# Sheet1.net
KiCad netlist of a schematic drawn in Altium Designer
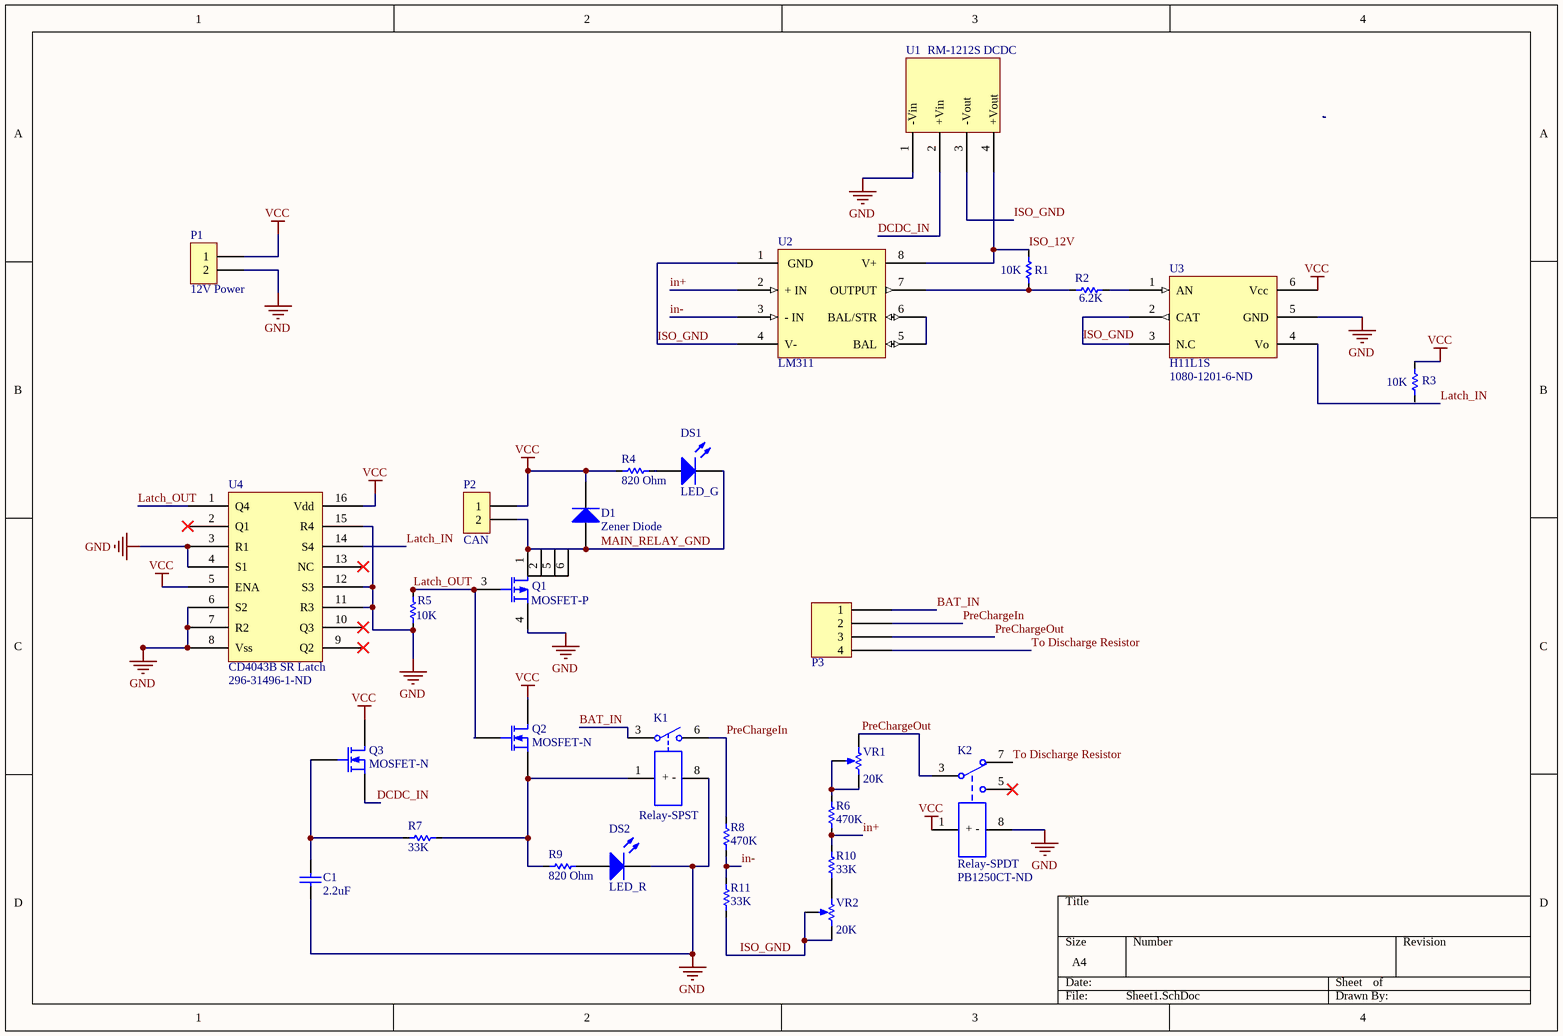
[diagram p0: Sheet1.SchDoc]

(export (version "E")
  (design (tool "Eeschema 10.0.6"))
  (components
    (comp (ref "C1")
      (value "2.2uF")
      (footprint "0603")
      (description "2.2µF ±10% 25V Ceramic Capacitor X5R 0603 (1608 Metric)")
      (fields
        (field (name "MANUFACTURERPARTNUMBER") "GRM188R61E225KA12D")
        (field (name "MANUFACTURER") "Murata Electronics North America")
      )
      (libsource (lib "Schematic Diagrams") (part "CAP CER 2.2UF 25V 10% 0603"))
    )
    (comp (ref "D1")
      (value "Zener Diode")
      (footprint "DO-214AA Diode")
      (description "Zener Diode 16V 5W ±5% Surface Mount DO-214AA (SMB)")
      (fields (field (name "MANUFACTURE PART NUMBER") "SMBJ5353B-TP"))
      (libsource (lib "Schematic Diagrams") (part "Zener Diode"))
    )
    (comp (ref "DS1")
      (value "LED_G")
      (footprint "LED_0603")
      (description "Green LED 0603")
      (fields (field (name "MANUFACTURE PART NUMBER") "LTST-C191KGKT"))
      (libsource (lib "Schematic Diagrams") (part "LED_G"))
    )
    (comp (ref "DS2")
      (value "LED_R")
      (footprint "LED_0603")
      (description "Red LED 0603")
      (fields (field (name "MANUFACTURE PART NUMBER") "LTST-C191KRKT"))
      (libsource (lib "Schematic Diagrams") (part "LED_R"))
    )
    (comp (ref "K1")
      (value "Relay-SPST")
      (footprint "MODULE4")
      (description "Telecom Relay SPST-NO (1 Form A) Surface Mount")
      (fields (field (name "MANUFACTURE PART NUMBER") "1462041-3"))
      (libsource (lib "Schematic Diagrams") (part "Relay-SPST"))
    )
    (comp (ref "K2")
      (value "Relay-SPDT")
      (footprint "RELAY_SPDT")
      (description "Telecom Relay SPDT (1 Form C) Surface Mount")
      (fields
        (field (name "SUPPLIER PART NUMBER 1") "PB1250CT-ND")
        (field (name "MANUFACTURER PART NUMBER") "1462042-9")
      )
      (libsource (lib "Schematic Diagrams") (part "Relay-SPDT"))
    )
    (comp (ref "P1")
      (value "12V Power")
      (footprint "WM9811CT-ND")
      (description "2 Position Receptacle Connector 0.059\" (1.50mm) Surface Mount Tin")
      (fields
        (field (name "DIGIKEY PART NUMBER") "WM9811CT-ND")
        (field (name "MANUFACTURER PART NUMBER") "5025840270")
      )
      (libsource (lib "Schematic Diagrams") (part "2 Position Clik-Mate 12V Connector"))
    )
    (comp (ref "P2")
      (value "CAN")
      (footprint "WM4780CT-ND")
      (description "2 Position Receptacle Connector 0.049\" (1.25mm) Surface Mount Tin")
      (fields
        (field (name "DIGIKEY PART NUMBER") "WM4780CT-ND")
        (field (name "MANUFACTURER PART NUMBER") "5023820270")
      )
      (libsource (lib "Schematic Diagrams") (part "2 Position Clik-Mate CAN Connector"))
    )
    (comp (ref "P3")
      (value "4 Position Clik-Mate HV Surface Mount")
      (footprint "WM2282CT-ND")
      (description "4 Position Receptacle Connector 0.079\" (2.00mm) Surface Mount, Right Angle Tin")
      (libsource (lib "Schematic Diagrams") (part "4 Position Clik-Mate HV Surface Mount"))
    )
    (comp (ref "Q1")
      (value "MOSFET-P")
      (footprint "P-MOSFET")
      (description "MOSFET P-CH 30V 4A SOT23-6")
      (fields
        (field (name "VENDOR PART NUMBER") "497-15521-1-ND")
        (field (name "MANUFACTURE PART NUMBER") "STT4P3LLH6")
      )
      (libsource (lib "Schematic Diagrams") (part "MOSFET-P"))
    )
    (comp (ref "Q2")
      (value "MOSFET-N")
      (footprint "N-CH MOSFET SOT-23")
      (description "MOSFET N-CH 50V 200MA SOT23-3")
      (fields
        (field (name "MANUFACTURE PART NUMBER") "BSS138-7-F")
        (field (name "VENDOR PART NUMBER") "497-3177-1-ND")
      )
      (libsource (lib "Schematic Diagrams") (part "MOSFET-N"))
    )
    (comp (ref "Q3")
      (value "MOSFET-N")
      (footprint "N-CH MOSFET SOT-23")
      (description "MOSFET N-CH 50V 200MA SOT23-3")
      (fields
        (field (name "MANUFACTURE PART NUMBER") "BSS138-7-F")
        (field (name "VENDOR PART NUMBER") "497-3177-1-ND")
      )
      (libsource (lib "Schematic Diagrams") (part "MOSFET-N"))
    )
    (comp (ref "R1")
      (value "10K")
      (footprint "RES_0603")
      (description "RES SMD 10K OHM 1% 1/10W 0603")
      (fields
        (field (name "MANUFACTURE PART NUMBER") "RC0603FR-0710KL")
        (field (name "VENDOR PART NUMBER") "311-10.0KHRCT-ND")
      )
      (libsource (lib "Schematic Diagrams") (part "RES SMD 10K OHM 1% 1/10W 0603"))
    )
    (comp (ref "R2")
      (value "6.2K")
      (footprint "RES_0603")
      (description "RES SMD 6.2K OHM 5% 1/10W 0603")
      (fields
        (field (name "MANUFACTURE PART NUMBER") "RC0603JR-076K2L")
        (field (name "VENDOR PART NUMBER") "311-6.2KGRCT-ND")
      )
      (libsource (lib "Schematic Diagrams") (part "RES SMD 6.2K OHM 5% 1/10W 0603"))
    )
    (comp (ref "R3")
      (value "10K")
      (footprint "RES_0603")
      (description "RES SMD 10K OHM 1% 1/10W 0603")
      (fields
        (field (name "MANUFACTURE PART NUMBER") "RC0603FR-0710KL")
        (field (name "VENDOR PART NUMBER") "311-10.0KHRCT-ND")
      )
      (libsource (lib "Schematic Diagrams") (part "RES SMD 10K OHM 1% 1/10W 0603"))
    )
    (comp (ref "R4")
      (value "820 Ohm")
      (footprint "RES_0603")
      (description "RES SMD 820 OHM 5% 1/4W 0603")
      (fields (field (name "MANUFACTURE PART NUMBER") "ESR03EZPJ821") (field (name "POWER") "1/10W"))
      (libsource (lib "Schematic Diagrams") (part "RES SMD 820 OHM 5% 1/4W 0603"))
    )
    (comp (ref "R5")
      (value "10K")
      (footprint "RES_0603")
      (description "RES SMD 10K OHM 1% 1/10W 0603")
      (fields
        (field (name "MANUFACTURE PART NUMBER") "RC0603FR-0710KL")
        (field (name "VENDOR PART NUMBER") "311-10.0KHRCT-ND")
      )
      (libsource (lib "Schematic Diagrams") (part "RES SMD 10K OHM 1% 1/10W 0603"))
    )
    (comp (ref "R6")
      (value "470K")
      (footprint "RES_0603")
      (description "RES SMD 470K OHM 1% 1/4W 0603")
      (fields (field (name "MANUFACTURE PART NUMBER") "ERJ-PA3F4703V") (field (name "POWER") "0.25W"))
      (libsource (lib "Schematic Diagrams") (part "RES 470K OHM 1% 1/4W 0603"))
    )
    (comp (ref "R7")
      (value "33K")
      (footprint "RES_0603")
      (description "RES 33K OHM 1% 1/4W 0603")
      (fields
        (field (name "MANUFACTURE PART NUMBER") "ERJ-PA3F3302V")
        (field (name "VENDOR PART NUMBER") "P47KBYCT-ND")
      )
      (libsource (lib "Schematic Diagrams") (part "RES 33K OHM 1% 1/4W 0603"))
    )
    (comp (ref "R8")
      (value "470K")
      (footprint "RES_0603")
      (description "RES SMD 470K OHM 1% 1/4W 0603")
      (fields (field (name "MANUFACTURE PART NUMBER") "ERJ-PA3F4703V") (field (name "POWER") "0.25W"))
      (libsource (lib "Schematic Diagrams") (part "RES 470K OHM 1% 1/4W 0603"))
    )
    (comp (ref "R9")
      (value "820 Ohm")
      (footprint "RES_0603")
      (description "RES SMD 820 OHM 5% 1/4W 0603")
      (fields (field (name "MANUFACTURE PART NUMBER") "ESR03EZPJ821") (field (name "POWER") "1/10W"))
      (libsource (lib "Schematic Diagrams") (part "RES SMD 820 OHM 5% 1/4W 0603"))
    )
    (comp (ref "R10")
      (value "33K")
      (footprint "RES_0603")
      (description "RES 33K OHM 1% 1/4W 0603")
      (fields
        (field (name "MANUFACTURE PART NUMBER") "ERJ-PA3F3302V")
        (field (name "VENDOR PART NUMBER") "P47KBYCT-ND")
      )
      (libsource (lib "Schematic Diagrams") (part "RES 33K OHM 1% 1/4W 0603"))
    )
    (comp (ref "R11")
      (value "33K")
      (footprint "RES_0603")
      (description "RES 33K OHM 1% 1/4W 0603")
      (fields
        (field (name "MANUFACTURE PART NUMBER") "ERJ-PA3F3302V")
        (field (name "VENDOR PART NUMBER") "P47KBYCT-ND")
      )
      (libsource (lib "Schematic Diagrams") (part "RES 33K OHM 1% 1/4W 0603"))
    )
    (comp (ref "U1")
      (value "RM-1212S DCDC")
      (footprint "RM-1212S")
      (libsource (lib "Schematic Diagrams") (part "RM-1212S DCDC"))
    )
    (comp (ref "U2") (value "LM311") (footprint "SOIC8") (libsource (lib "Library") (part "LM311")))
    (comp (ref "U3")
      (value "H11L1S")
      (footprint "H11LS")
      (description "OPTOISO 5KV OPEN COLLECTOR 6SMD")
      (fields (field (name "SUPPLIER PART NUMBER 1") "1080-1201-6-ND"))
      (libsource (lib "Schematic Diagrams") (part "H11L1S"))
    )
    (comp (ref "U4")
      (value "CD4043B SR Latch")
      (footprint "CD4043BDR-16SOIC")
      (description "S-R Latch 4 Channel 1:1 IC Tri-State 16-TSSOP")
      (fields (field (name "SUPPLIER PART NUMBER 1") "296-31496-1-ND"))
      (libsource (lib "Schematic Diagrams") (part "CD4043B SR Latch"))
    )
    (comp (ref "VR1")
      (value "20K")
      (footprint "20K POT")
      (description "20k Ohm 0.25W, 1/4W Gull Wing Surface Mount Trimmer Potentiometer")
      (fields (field (name "POWER") "1/4W") (field (name "MANUFACTURE PART NUMBER") "23BR20KLFTR"))
      (libsource (lib "Schematic Diagrams") (part "20k 0.25W Pot"))
    )
    (comp (ref "VR2")
      (value "20K")
      (footprint "20K POT")
      (description "20k Ohm 0.25W, 1/4W Gull Wing Surface Mount Trimmer Potentiometer")
      (fields (field (name "POWER") "1/4W") (field (name "MANUFACTURE PART NUMBER") "23BR20KLFTR"))
      (libsource (lib "Schematic Diagrams") (part "20k 0.25W Pot"))
    )
  )
  (nets
    (net (code "1") (name "/BAT_IN") (class "Default")
      (node (ref "K1") (pin "3") (pinfunction "3_3") (pintype "passive"))
      (node (ref "P3") (pin "1") (pinfunction "1_1") (pintype "passive"))
    )
    (net (code "2") (name "/DCDC_IN") (class "Default")
      (node (ref "Q3") (pin "2") (pinfunction "S_2") (pintype "passive"))
      (node (ref "U1") (pin "2") (pinfunction "+Vin_2") (pintype "passive"))
    )
    (net (code "3") (name "/ISO_12V") (class "Default")
      (node (ref "R1") (pin "2") (pinfunction "2_2") (pintype "passive"))
      (node (ref "U1") (pin "4") (pinfunction "+Vout_4") (pintype "passive"))
      (node (ref "U2") (pin "8") (pinfunction "V+_8") (pintype "power_in"))
    )
    (net (code "4") (name "/ISO_GND") (class "Default")
      (node (ref "R11") (pin "1") (pinfunction "1_1") (pintype "passive"))
      (node (ref "U1") (pin "3") (pinfunction "-Vout_3") (pintype "passive"))
      (node (ref "U2") (pin "1") (pinfunction "GND_1") (pintype "power_in"))
      (node (ref "U2") (pin "4") (pinfunction "V-_4") (pintype "power_in"))
      (node (ref "U3") (pin "2") (pinfunction "CAT_2") (pintype "output"))
      (node (ref "U3") (pin "3") (pinfunction "N.C_3") (pintype "passive"))
      (node (ref "VR2") (pin "2") (pinfunction "TAP_2") (pintype "passive"))
      (node (ref "VR2") (pin "3") (pinfunction "BOT_3") (pintype "passive"))
    )
    (net (code "5") (name "/Latch_IN") (class "Default")
      (node (ref "U3") (pin "4") (pinfunction "Vo_4") (pintype "passive"))
      (node (ref "U4") (pin "14") (pinfunction "S4_14") (pintype "passive"))
    )
    (net (code "6") (name "/Latch_OUT") (class "Default")
      (node (ref "Q1") (pin "3") (pinfunction "G_3") (pintype "passive"))
      (node (ref "Q2") (pin "1") (pinfunction "G_1") (pintype "passive"))
      (node (ref "R5") (pin "2") (pinfunction "2_2") (pintype "passive"))
      (node (ref "U4") (pin "1") (pinfunction "Q4_1") (pintype "passive"))
    )
    (net (code "7") (name "/MAIN_RELAY_GND") (class "Default")
      (node (ref "D1") (pin "1") (pinfunction "A_1") (pintype "passive"))
      (node (ref "DS1") (pin "2") (pinfunction "K_2") (pintype "passive"))
      (node (ref "P2") (pin "2") (pinfunction "2_2") (pintype "passive"))
      (node (ref "Q1") (pin "1") (pinfunction "D_1") (pintype "passive"))
    )
    (net (code "8") (name "/PreChargeIn") (class "Default")
      (node (ref "K1") (pin "6") (pinfunction "6_6") (pintype "passive"))
      (node (ref "P3") (pin "2") (pinfunction "2_2") (pintype "passive"))
      (node (ref "R8") (pin "2") (pinfunction "2_2") (pintype "passive"))
    )
    (net (code "9") (name "/PreChargeOut") (class "Default")
      (node (ref "K2") (pin "3") (pinfunction "3_3") (pintype "passive"))
      (node (ref "P3") (pin "3") (pinfunction "3_3") (pintype "passive"))
      (node (ref "VR1") (pin "1") (pinfunction "TOP_1") (pintype "passive"))
    )
    (net (code "10") (name "/To Discharge Resistor") (class "Default")
      (node (ref "K2") (pin "7") (pinfunction "7_7") (pintype "passive"))
      (node (ref "P3") (pin "4") (pinfunction "4_4") (pintype "passive"))
    )
    (net (code "11") (name "/in+") (class "Default")
      (node (ref "R10") (pin "2") (pinfunction "2_2") (pintype "passive"))
      (node (ref "R6") (pin "1") (pinfunction "1_1") (pintype "passive"))
      (node (ref "U2") (pin "2") (pinfunction "+_IN_2") (pintype "input"))
    )
    (net (code "12") (name "/in-") (class "Default")
      (node (ref "R11") (pin "2") (pinfunction "2_2") (pintype "passive"))
      (node (ref "R8") (pin "1") (pinfunction "1_1") (pintype "passive"))
      (node (ref "U2") (pin "3") (pinfunction "-_IN_3") (pintype "input"))
    )
    (net (code "13") (name "GND") (class "Default")
      (node (ref "C1") (pin "1") (pinfunction "1_1") (pintype "passive"))
      (node (ref "DS2") (pin "2") (pinfunction "K_2") (pintype "passive"))
      (node (ref "K1") (pin "8") (pinfunction "-_8") (pintype "passive"))
      (node (ref "K2") (pin "8") (pinfunction "-_8") (pintype "passive"))
      (node (ref "P1") (pin "2") (pinfunction "2_2") (pintype "passive"))
      (node (ref "Q1") (pin "4") (pinfunction "S_4") (pintype "passive"))
      (node (ref "R5") (pin "1") (pinfunction "1_1") (pintype "passive"))
      (node (ref "U1") (pin "1") (pinfunction "-Vin_1") (pintype "passive"))
      (node (ref "U3") (pin "5") (pinfunction "GND_5") (pintype "passive"))
      (node (ref "U4") (pin "11") (pinfunction "R3_11") (pintype "passive"))
      (node (ref "U4") (pin "12") (pinfunction "S3_12") (pintype "passive"))
      (node (ref "U4") (pin "15") (pinfunction "R4_15") (pintype "passive"))
      (node (ref "U4") (pin "3") (pinfunction "R1_3") (pintype "passive"))
      (node (ref "U4") (pin "4") (pinfunction "S1_4") (pintype "passive"))
      (node (ref "U4") (pin "6") (pinfunction "S2_6") (pintype "passive"))
      (node (ref "U4") (pin "7") (pinfunction "R2_7") (pintype "passive"))
      (node (ref "U4") (pin "8") (pinfunction "Vss_8") (pintype "passive"))
    )
    (net (code "14") (name "Net-(DS1-A)") (class "Default")
      (node (ref "DS1") (pin "1") (pinfunction "A_1") (pintype "passive"))
      (node (ref "R4") (pin "2") (pinfunction "2_2") (pintype "passive"))
    )
    (net (code "15") (name "Net-(DS2-A)") (class "Default")
      (node (ref "DS2") (pin "1") (pinfunction "A_1") (pintype "passive"))
      (node (ref "R9") (pin "2") (pinfunction "2_2") (pintype "passive"))
    )
    (net (code "16") (name "Net-(K1-+)") (class "Default")
      (node (ref "K1") (pin "1") (pinfunction "+_1") (pintype "passive"))
      (node (ref "Q2") (pin "2") (pinfunction "S_2") (pintype "passive"))
      (node (ref "R7") (pin "1") (pinfunction "1_1") (pintype "passive"))
      (node (ref "R9") (pin "1") (pinfunction "1_1") (pintype "passive"))
    )
    (net (code "17") (name "Net-(Q3-G)") (class "Default")
      (node (ref "C1") (pin "2") (pinfunction "2_2") (pintype "passive"))
      (node (ref "Q3") (pin "1") (pinfunction "G_1") (pintype "passive"))
      (node (ref "R7") (pin "2") (pinfunction "2_2") (pintype "passive"))
    )
    (net (code "18") (name "Net-(U2-BAL)") (class "Default")
      (node (ref "U2") (pin "5") (pinfunction "BAL_5") (pintype "bidirectional"))
      (node (ref "U2") (pin "6") (pinfunction "BAL/STR_6") (pintype "bidirectional"))
    )
    (net (code "19") (name "Net-(U2-OUTPUT)") (class "Default")
      (node (ref "R1") (pin "1") (pinfunction "1_1") (pintype "passive"))
      (node (ref "R2") (pin "1") (pinfunction "1_1") (pintype "passive"))
      (node (ref "U2") (pin "7") (pinfunction "OUTPUT_7") (pintype "output"))
    )
    (net (code "20") (name "Net-(U3-AN)") (class "Default")
      (node (ref "R2") (pin "2") (pinfunction "2_2") (pintype "passive"))
      (node (ref "U3") (pin "1") (pinfunction "AN_1") (pintype "input"))
    )
    (net (code "21") (name "Net-(VR1-BOT)") (class "Default")
      (node (ref "R6") (pin "2") (pinfunction "2_2") (pintype "passive"))
      (node (ref "VR1") (pin "2") (pinfunction "TAP_2") (pintype "passive"))
      (node (ref "VR1") (pin "3") (pinfunction "BOT_3") (pintype "passive"))
    )
    (net (code "22") (name "Net-(VR2-TOP)") (class "Default")
      (node (ref "R10") (pin "1") (pinfunction "1_1") (pintype "passive"))
      (node (ref "VR2") (pin "1") (pinfunction "TOP_1") (pintype "passive"))
    )
    (net (code "23") (name "VCC") (class "Default")
      (node (ref "D1") (pin "2") (pinfunction "K_2") (pintype "passive"))
      (node (ref "K2") (pin "1") (pinfunction "+_1") (pintype "passive"))
      (node (ref "P1") (pin "1") (pinfunction "1_1") (pintype "passive"))
      (node (ref "P2") (pin "1") (pinfunction "1_1") (pintype "passive"))
      (node (ref "Q2") (pin "3") (pinfunction "D_3") (pintype "passive"))
      (node (ref "Q3") (pin "3") (pinfunction "D_3") (pintype "passive"))
      (node (ref "R3") (pin "2") (pinfunction "2_2") (pintype "passive"))
      (node (ref "R4") (pin "1") (pinfunction "1_1") (pintype "passive"))
      (node (ref "U3") (pin "6") (pinfunction "Vcc_6") (pintype "passive"))
      (node (ref "U4") (pin "16") (pinfunction "Vdd_16") (pintype "passive"))
      (node (ref "U4") (pin "5") (pinfunction "ENA_5") (pintype "passive"))
    )
    (net (code "24") (name "unconnected-(K2-Pad5)") (class "Default")
      (node (ref "K2") (pin "5") (pinfunction "5_5") (pintype "passive+no_connect"))
    )
    (net (code "25") (name "unconnected-(Q1-D-Pad2)") (class "Default")
      (node (ref "Q1") (pin "2") (pinfunction "D_2") (pintype "passive"))
    )
    (net (code "26") (name "unconnected-(Q1-D-Pad5)") (class "Default")
      (node (ref "Q1") (pin "5") (pinfunction "D_5") (pintype "passive"))
    )
    (net (code "27") (name "unconnected-(Q1-D-Pad6)") (class "Default")
      (node (ref "Q1") (pin "6") (pinfunction "D_6") (pintype "passive"))
    )
    (net (code "28") (name "unconnected-(R3-Pad1)") (class "Default")
      (node (ref "R3") (pin "1") (pinfunction "1_1") (pintype "passive"))
    )
    (net (code "29") (name "unconnected-(U4-NC-Pad13)") (class "Default")
      (node (ref "U4") (pin "13") (pinfunction "NC_13") (pintype "passive+no_connect"))
    )
    (net (code "30") (name "unconnected-(U4-Q1-Pad2)") (class "Default")
      (node (ref "U4") (pin "2") (pinfunction "Q1_2") (pintype "passive+no_connect"))
    )
    (net (code "31") (name "unconnected-(U4-Q2-Pad9)") (class "Default")
      (node (ref "U4") (pin "9") (pinfunction "Q2_9") (pintype "passive+no_connect"))
    )
    (net (code "32") (name "unconnected-(U4-Q3-Pad10)") (class "Default")
      (node (ref "U4") (pin "10") (pinfunction "Q3_10") (pintype "passive+no_connect"))
    )
  )
)
